# button.net
KiCad netlist of a schematic drawn in EAGLE
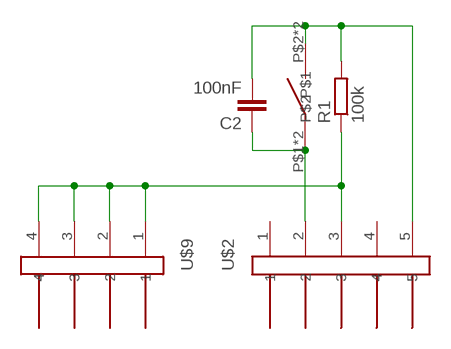
[diagram p0: schematic, sheet 1]

(export (version "E")
  (design (tool "Eeschema 10.0.6"))
  (components
    (comp (ref "C2")
      (value "100nF")
      (footprint "eagle-import:C0603K")
      (libsource (lib "eagle-import") (part "C-EUC0603K"))
    )
    (comp (ref "R1")
      (value "100k")
      (footprint "eagle-import:R0603")
      (libsource (lib "eagle-import") (part "R-EU_R0603"))
    )
    (comp (ref "U$1")
      (value "BUTTON_6.3X6.3")
      (footprint "eagle-import:BUTTON_6.2X6.2")
      (libsource (lib "eagle-import") (part "BUTTON_6.3X6.3"))
    )
    (comp (ref "U$2")
      (value "JUMPER5M")
      (footprint "eagle-import:JUMPER5M")
      (libsource (lib "eagle-import") (part "JUMPER5M"))
    )
    (comp (ref "U$9")
      (value "JUMPER4M")
      (footprint "eagle-import:JUMPER4M")
      (libsource (lib "eagle-import") (part "JUMPER4M"))
    )
  )
  (nets
    (net (code "1") (name "Net-(C2-Pad1)") (class "Default")
      (node (ref "C2") (pin "1") (pinfunction "1_1") (pintype "passive"))
      (node (ref "U$1") (pin "P$1") (pinfunction "P$1_P$1") (pintype "bidirectional"))
      (node (ref "U$1") (pin "P$3") (pinfunction "P$1_P$3") (pintype "bidirectional"))
      (node (ref "U$2") (pin "2") (pinfunction "2_2") (pintype "bidirectional"))
    )
    (net (code "2") (name "Net-(C2-Pad2)") (class "Default")
      (node (ref "C2") (pin "2") (pinfunction "2_2") (pintype "passive"))
      (node (ref "R1") (pin "2") (pinfunction "2_2") (pintype "passive"))
      (node (ref "U$1") (pin "P$2") (pinfunction "P$2_P$2") (pintype "bidirectional"))
      (node (ref "U$1") (pin "P$4") (pinfunction "P$2_P$4") (pintype "bidirectional"))
      (node (ref "U$2") (pin "5") (pinfunction "5_5") (pintype "bidirectional"))
    )
    (net (code "3") (name "Net-(R1-Pad1)") (class "Default")
      (node (ref "R1") (pin "1") (pinfunction "1_1") (pintype "passive"))
      (node (ref "U$2") (pin "3") (pinfunction "3_3") (pintype "bidirectional"))
      (node (ref "U$9") (pin "1") (pinfunction "1_1") (pintype "bidirectional"))
      (node (ref "U$9") (pin "2") (pinfunction "2_2") (pintype "bidirectional"))
      (node (ref "U$9") (pin "3") (pinfunction "3_3") (pintype "bidirectional"))
      (node (ref "U$9") (pin "4") (pinfunction "4_4") (pintype "bidirectional"))
    )
    (net (code "4") (name "unconnected-(U$2-Pad1)") (class "Default")
      (node (ref "U$2") (pin "1") (pinfunction "1_1") (pintype "bidirectional"))
    )
    (net (code "5") (name "unconnected-(U$2-Pad4)") (class "Default")
      (node (ref "U$2") (pin "4") (pinfunction "4_4") (pintype "bidirectional"))
    )
  )
)
